# 51.net
KiCad netlist of a schematic drawn in EasyEDA Pro
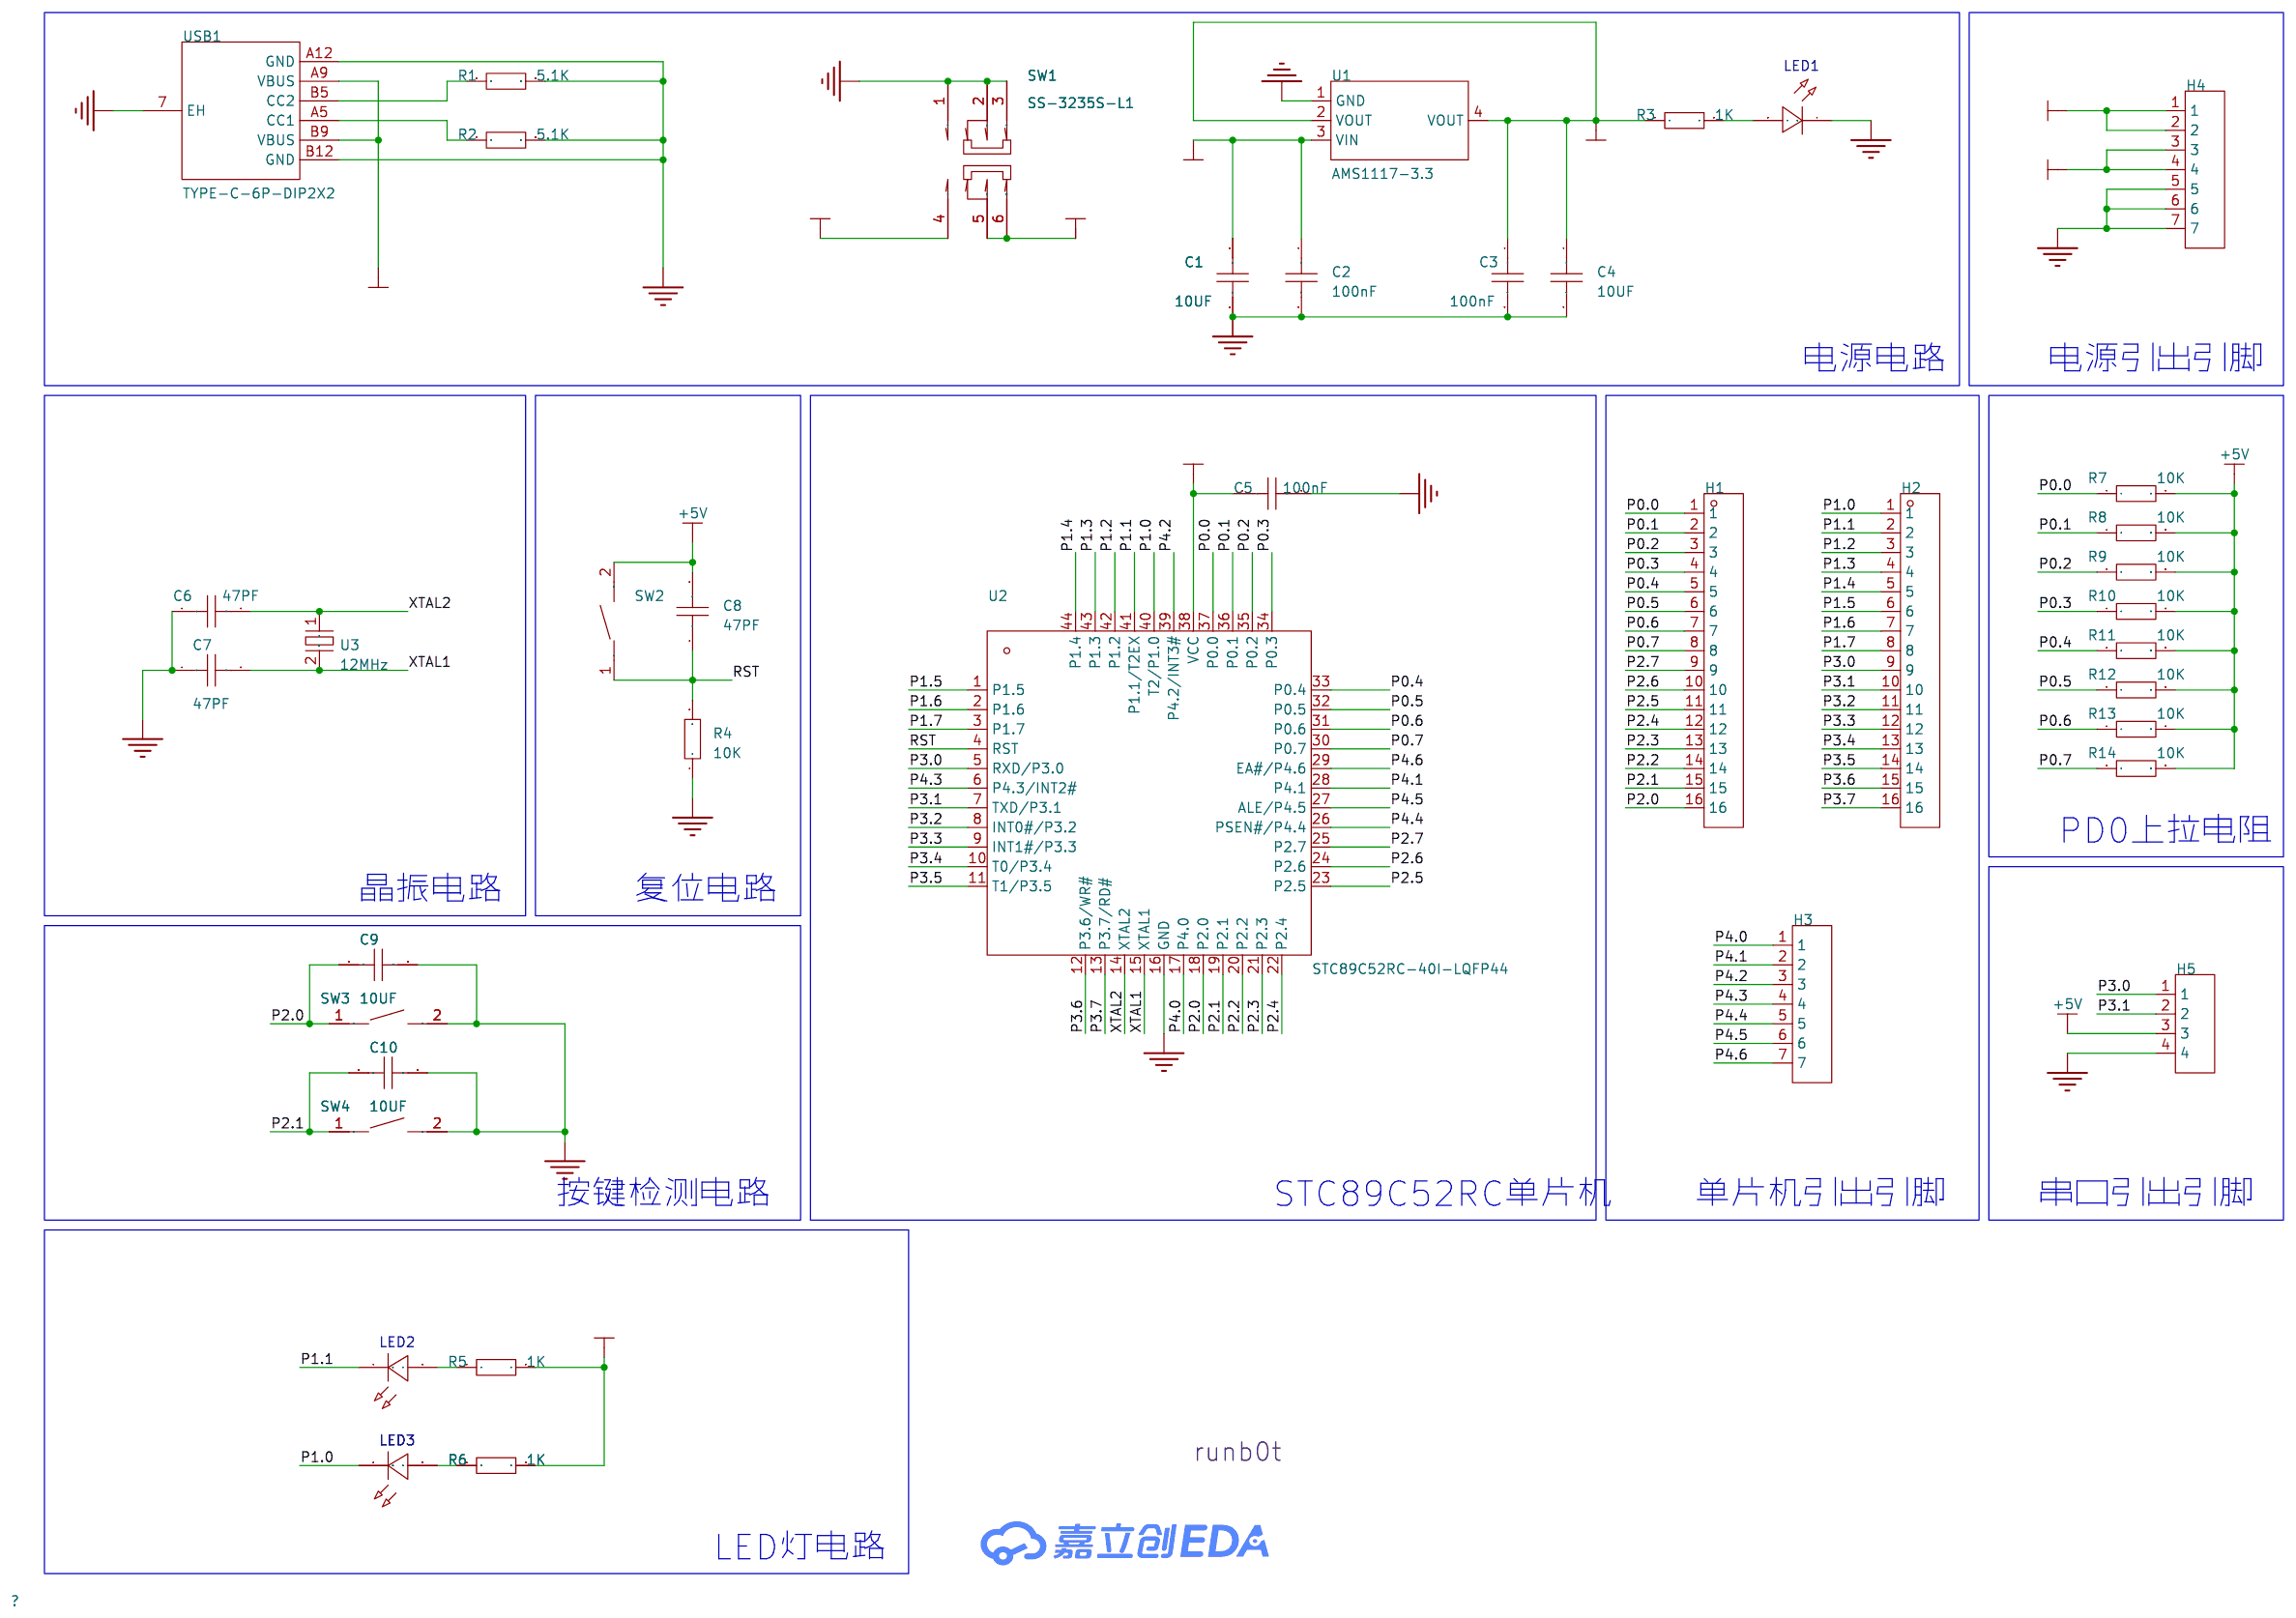
[diagram p0: schematic sheet]

(export (version "E")
  (design (tool "Eeschema 10.0.6"))
  (components
    (comp (ref "C1")
      (value "10UF")
      (footprint "easyedapro:C0805")
      (libsource (lib "easyedapro") (part "CapAcitance"))
    )
    (comp (ref "C2")
      (value "100nF")
      (footprint "easyedapro:C0805")
      (libsource (lib "easyedapro") (part "CapAcitance"))
    )
    (comp (ref "C3")
      (value "100nF")
      (footprint "easyedapro:C0805")
      (libsource (lib "easyedapro") (part "CapAcitance"))
    )
    (comp (ref "C4")
      (value "10UF")
      (footprint "easyedapro:C0805")
      (libsource (lib "easyedapro") (part "CapAcitance"))
    )
    (comp (ref "C5")
      (value "100nF")
      (footprint "easyedapro:C0805")
      (libsource (lib "easyedapro") (part "CapAcitance"))
    )
    (comp (ref "C6")
      (value "47PF")
      (footprint "easyedapro:C0805")
      (libsource (lib "easyedapro") (part "CapAcitance"))
    )
    (comp (ref "C7")
      (value "47PF")
      (footprint "easyedapro:C0805")
      (libsource (lib "easyedapro") (part "CapAcitance"))
    )
    (comp (ref "C8")
      (value "47PF")
      (footprint "easyedapro:C0805")
      (libsource (lib "easyedapro") (part "CapAcitance"))
    )
    (comp (ref "C9")
      (value "10UF")
      (footprint "easyedapro:C0805")
      (libsource (lib "easyedapro") (part "CapAcitance"))
    )
    (comp (ref "C10")
      (value "10UF")
      (footprint "easyedapro:C0805")
      (libsource (lib "easyedapro") (part "CapAcitance"))
    )
    (comp (ref "H1")
      (value "~")
      (footprint "easyedapro:HDR-TH_16P-P2.54-V-M")
      (libsource (lib "easyedapro") (part "HDR_2.54-1x16P"))
    )
    (comp (ref "H2")
      (value "~")
      (footprint "easyedapro:HDR-TH_16P-P2.54-V-M")
      (libsource (lib "easyedapro") (part "HDR_2.54-1x16P"))
    )
    (comp (ref "H3")
      (value "~")
      (footprint "easyedapro:HDR-TH_7P-P2.54-V-M")
      (libsource (lib "easyedapro") (part "PZ254V-11-07P"))
    )
    (comp (ref "H4")
      (value "~")
      (footprint "easyedapro:HDR-TH_7P-P2.54-V-M")
      (libsource (lib "easyedapro") (part "PZ254V-11-07P"))
    )
    (comp (ref "H5")
      (value "~")
      (footprint "easyedapro:HDR-TH_4P-P2.54-V-M")
      (libsource (lib "easyedapro") (part "PZ254V-11-04P"))
    )
    (comp (ref "LED1")
      (value "~")
      (footprint "easyedapro:LED_0805")
      (libsource (lib "easyedapro") (part "LED_G"))
    )
    (comp (ref "LED2")
      (value "~")
      (footprint "easyedapro:LED_0805")
      (libsource (lib "easyedapro") (part "LED_G"))
    )
    (comp (ref "LED3")
      (value "~")
      (footprint "easyedapro:LED_0805")
      (libsource (lib "easyedapro") (part "LED_G"))
    )
    (comp (ref "R1") (value "5.1K") (footprint "easyedapro:R0805") (libsource (lib "easyedapro") (part "电阻")))
    (comp (ref "R2") (value "5.1K") (footprint "easyedapro:R0805") (libsource (lib "easyedapro") (part "电阻")))
    (comp (ref "R3") (value "1K") (footprint "easyedapro:R0805") (libsource (lib "easyedapro") (part "电阻")))
    (comp (ref "R4") (value "10K") (footprint "easyedapro:R0805") (libsource (lib "easyedapro") (part "电阻")))
    (comp (ref "R5") (value "1K") (footprint "easyedapro:R0805") (libsource (lib "easyedapro") (part "电阻")))
    (comp (ref "R6") (value "1K") (footprint "easyedapro:R0805") (libsource (lib "easyedapro") (part "电阻")))
    (comp (ref "R7") (value "10K") (footprint "easyedapro:R0805") (libsource (lib "easyedapro") (part "电阻")))
    (comp (ref "R8") (value "10K") (footprint "easyedapro:R0805") (libsource (lib "easyedapro") (part "电阻")))
    (comp (ref "R9") (value "10K") (footprint "easyedapro:R0805") (libsource (lib "easyedapro") (part "电阻")))
    (comp (ref "R10") (value "10K") (footprint "easyedapro:R0805") (libsource (lib "easyedapro") (part "电阻")))
    (comp (ref "R11") (value "10K") (footprint "easyedapro:R0805") (libsource (lib "easyedapro") (part "电阻")))
    (comp (ref "R12") (value "10K") (footprint "easyedapro:R0805") (libsource (lib "easyedapro") (part "电阻")))
    (comp (ref "R13") (value "10K") (footprint "easyedapro:R0805") (libsource (lib "easyedapro") (part "电阻")))
    (comp (ref "R14") (value "10K") (footprint "easyedapro:R0805") (libsource (lib "easyedapro") (part "电阻")))
    (comp (ref "SW1")
      (value "SS-3235S-L1")
      (footprint "easyedapro:SW-SMD_SS-3235S-LX")
      (description "电路结构:双刀双掷;安装方式:卧贴;开关颜色:黑色;额定电流(DC):50mA;额定电压(DC):12V;额定电流(AC):50mA;额定电压(AC):12V;机械寿命:1万次;")
      (fields (field (name "Manufacturer") "XKB Connectivity(中国星坤)"))
      (libsource (lib "easyedapro") (part "SS-3235S-L1"))
    )
    (comp (ref "SW2")
      (value "轻触按键3*4*H")
      (footprint "easyedapro:SW-SMD_L4.0-W2.9-LS5.0")
      (libsource (lib "easyedapro") (part "轻触按键3*4*H"))
    )
    (comp (ref "SW3")
      (value "轻触按键3*4*H")
      (footprint "easyedapro:SW-SMD_L4.0-W2.9-LS5.0")
      (libsource (lib "easyedapro") (part "轻触按键3*4*H"))
    )
    (comp (ref "SW4")
      (value "轻触按键3*4*H")
      (footprint "easyedapro:SW-SMD_L4.0-W2.9-LS5.0")
      (libsource (lib "easyedapro") (part "轻触按键3*4*H"))
    )
    (comp (ref "U1")
      (value "AMS1117-3.3")
      (footprint "easyedapro:SOT-223-3_L6.5-W3.4-P2.30-LS7.0-BR")
      (description "输出类型:固定;工作电压:-;输出电压:3.3V;输出电流:1A;电源纹波抑制比(PSRR):72dB@(120Hz);输出极性:正极;")
      (fields (field (name "Manufacturer") "AMS"))
      (libsource (lib "easyedapro") (part "AMS1117-3.3"))
    )
    (comp (ref "U2")
      (value "STC89C52RC-40I-LQFP44")
      (footprint "easyedapro:LQFP-44_L10.0-W10.0-P0.80-LS12.0-BL")
      (description "CPU内核:51系列;应用领域:-;")
      (fields (field (name "Manufacturer") "STC"))
      (libsource (lib "easyedapro") (part "STC89C52RC-40I_C8707"))
    )
    (comp (ref "U3")
      (value "12MHz")
      (footprint "easyedapro:CRYSTAL-SMD_L11.4-W4.7-LS12.7")
      (description "频率:12MHz;常温频差:±30ppm;外接负载电容:18pF;频率稳定度(全温):±35ppm;")
      (fields
        (field (name "Manufacturer Part") "ABLS-12.000MHZ-B4H-T")
        (field (name "Manufacturer") "ABRACON")
      )
      (libsource (lib "easyedapro") (part "ABLS-12.000MHZ-B4H-T"))
    )
    (comp (ref "USB1")
      (value "TYPE-C-6P-DIP2X2")
      (footprint "easyedapro:TYPE-C-SMD_TYPE-C-6P")
      (libsource (lib "easyedapro") (part "TYPE-C-6P-DIP2X2"))
    )
  )
  (nets
    (net (code "1") (name "+5V") (class "Default")
      (node (ref "C1") (pin "1") (pinfunction "1_1") (pintype "input"))
      (node (ref "C2") (pin "1") (pinfunction "1_1") (pintype "input"))
      (node (ref "C5") (pin "1") (pinfunction "1_1") (pintype "input"))
      (node (ref "C8") (pin "2") (pinfunction "2_2") (pintype "input"))
      (node (ref "H4") (pin "1") (pinfunction "1_1") (pintype "unspecified"))
      (node (ref "H4") (pin "2") (pinfunction "2_2") (pintype "unspecified"))
      (node (ref "H5") (pin "3") (pinfunction "3_3") (pintype "unspecified"))
      (node (ref "R10") (pin "2") (pinfunction "2_2") (pintype "input"))
      (node (ref "R11") (pin "2") (pinfunction "2_2") (pintype "input"))
      (node (ref "R12") (pin "2") (pinfunction "2_2") (pintype "input"))
      (node (ref "R13") (pin "2") (pinfunction "2_2") (pintype "input"))
      (node (ref "R14") (pin "2") (pinfunction "2_2") (pintype "input"))
      (node (ref "R7") (pin "2") (pinfunction "2_2") (pintype "input"))
      (node (ref "R8") (pin "2") (pinfunction "2_2") (pintype "input"))
      (node (ref "R9") (pin "2") (pinfunction "2_2") (pintype "input"))
      (node (ref "SW1") (pin "5") (pinfunction "5_5") (pintype "unspecified"))
      (node (ref "SW1") (pin "6") (pinfunction "6_6") (pintype "unspecified"))
      (node (ref "SW2") (pin "2") (pinfunction "2_2") (pintype "unspecified"))
      (node (ref "U1") (pin "3") (pinfunction "VIN_3") (pintype "unspecified"))
      (node (ref "U2") (pin "38") (pinfunction "VCC_38") (pintype "unspecified"))
    )
    (net (code "2") (name "/P0.0") (class "Default")
      (node (ref "H1") (pin "1") (pinfunction "1_1") (pintype "input"))
      (node (ref "R7") (pin "1") (pinfunction "1_1") (pintype "input"))
      (node (ref "U2") (pin "37") (pinfunction "P0.0_37") (pintype "unspecified"))
    )
    (net (code "3") (name "/P0.1") (class "Default")
      (node (ref "H1") (pin "2") (pinfunction "2_2") (pintype "input"))
      (node (ref "R8") (pin "1") (pinfunction "1_1") (pintype "input"))
      (node (ref "U2") (pin "36") (pinfunction "P0.1_36") (pintype "unspecified"))
    )
    (net (code "4") (name "/P0.2") (class "Default")
      (node (ref "H1") (pin "3") (pinfunction "3_3") (pintype "input"))
      (node (ref "R9") (pin "1") (pinfunction "1_1") (pintype "input"))
      (node (ref "U2") (pin "35") (pinfunction "P0.2_35") (pintype "unspecified"))
    )
    (net (code "5") (name "/P0.3") (class "Default")
      (node (ref "H1") (pin "4") (pinfunction "4_4") (pintype "input"))
      (node (ref "R10") (pin "1") (pinfunction "1_1") (pintype "input"))
      (node (ref "U2") (pin "34") (pinfunction "P0.3_34") (pintype "unspecified"))
    )
    (net (code "6") (name "/P0.4") (class "Default")
      (node (ref "H1") (pin "5") (pinfunction "5_5") (pintype "input"))
      (node (ref "R11") (pin "1") (pinfunction "1_1") (pintype "input"))
      (node (ref "U2") (pin "33") (pinfunction "P0.4_33") (pintype "unspecified"))
    )
    (net (code "7") (name "/P0.5") (class "Default")
      (node (ref "H1") (pin "6") (pinfunction "6_6") (pintype "input"))
      (node (ref "R12") (pin "1") (pinfunction "1_1") (pintype "input"))
      (node (ref "U2") (pin "32") (pinfunction "P0.5_32") (pintype "unspecified"))
    )
    (net (code "8") (name "/P0.6") (class "Default")
      (node (ref "H1") (pin "7") (pinfunction "7_7") (pintype "input"))
      (node (ref "R13") (pin "1") (pinfunction "1_1") (pintype "input"))
      (node (ref "U2") (pin "31") (pinfunction "P0.6_31") (pintype "unspecified"))
    )
    (net (code "9") (name "/P0.7") (class "Default")
      (node (ref "H1") (pin "8") (pinfunction "8_8") (pintype "input"))
      (node (ref "R14") (pin "1") (pinfunction "1_1") (pintype "input"))
      (node (ref "U2") (pin "30") (pinfunction "P0.7_30") (pintype "unspecified"))
    )
    (net (code "10") (name "/P1.0") (class "Default")
      (node (ref "H2") (pin "1") (pinfunction "1_1") (pintype "input"))
      (node (ref "LED3") (pin "1") (pinfunction "C_1") (pintype "input"))
      (node (ref "U2") (pin "40") (pinfunction "T2/P1.0_40") (pintype "unspecified"))
    )
    (net (code "11") (name "/P1.1") (class "Default")
      (node (ref "H2") (pin "2") (pinfunction "2_2") (pintype "input"))
      (node (ref "LED2") (pin "1") (pinfunction "C_1") (pintype "input"))
      (node (ref "U2") (pin "41") (pinfunction "P1.1/T2EX_41") (pintype "unspecified"))
    )
    (net (code "12") (name "/P1.2") (class "Default")
      (node (ref "H2") (pin "3") (pinfunction "3_3") (pintype "input"))
      (node (ref "U2") (pin "42") (pinfunction "P1.2_42") (pintype "unspecified"))
    )
    (net (code "13") (name "/P1.3") (class "Default")
      (node (ref "H2") (pin "4") (pinfunction "4_4") (pintype "input"))
      (node (ref "U2") (pin "43") (pinfunction "P1.3_43") (pintype "unspecified"))
    )
    (net (code "14") (name "/P1.4") (class "Default")
      (node (ref "H2") (pin "5") (pinfunction "5_5") (pintype "input"))
      (node (ref "U2") (pin "44") (pinfunction "P1.4_44") (pintype "unspecified"))
    )
    (net (code "15") (name "/P1.5") (class "Default")
      (node (ref "H2") (pin "6") (pinfunction "6_6") (pintype "input"))
      (node (ref "U2") (pin "1") (pinfunction "P1.5_1") (pintype "unspecified"))
    )
    (net (code "16") (name "/P1.6") (class "Default")
      (node (ref "H2") (pin "7") (pinfunction "7_7") (pintype "input"))
      (node (ref "U2") (pin "2") (pinfunction "P1.6_2") (pintype "unspecified"))
    )
    (net (code "17") (name "/P1.7") (class "Default")
      (node (ref "H2") (pin "8") (pinfunction "8_8") (pintype "input"))
      (node (ref "U2") (pin "3") (pinfunction "P1.7_3") (pintype "unspecified"))
    )
    (net (code "18") (name "/P2.0") (class "Default")
      (node (ref "C9") (pin "1") (pinfunction "1_1") (pintype "input"))
      (node (ref "H1") (pin "16") (pinfunction "16_16") (pintype "input"))
      (node (ref "SW3") (pin "1") (pinfunction "1_1") (pintype "unspecified"))
      (node (ref "U2") (pin "18") (pinfunction "P2.0_18") (pintype "unspecified"))
    )
    (net (code "19") (name "/P2.1") (class "Default")
      (node (ref "C10") (pin "1") (pinfunction "1_1") (pintype "input"))
      (node (ref "H1") (pin "15") (pinfunction "15_15") (pintype "input"))
      (node (ref "SW4") (pin "1") (pinfunction "1_1") (pintype "unspecified"))
      (node (ref "U2") (pin "19") (pinfunction "P2.1_19") (pintype "unspecified"))
    )
    (net (code "20") (name "/P2.2") (class "Default")
      (node (ref "H1") (pin "14") (pinfunction "14_14") (pintype "input"))
      (node (ref "U2") (pin "20") (pinfunction "P2.2_20") (pintype "unspecified"))
    )
    (net (code "21") (name "/P2.3") (class "Default")
      (node (ref "H1") (pin "13") (pinfunction "13_13") (pintype "input"))
      (node (ref "U2") (pin "21") (pinfunction "P2.3_21") (pintype "unspecified"))
    )
    (net (code "22") (name "/P2.4") (class "Default")
      (node (ref "H1") (pin "12") (pinfunction "12_12") (pintype "input"))
      (node (ref "U2") (pin "22") (pinfunction "P2.4_22") (pintype "unspecified"))
    )
    (net (code "23") (name "/P2.5") (class "Default")
      (node (ref "H1") (pin "11") (pinfunction "11_11") (pintype "input"))
      (node (ref "U2") (pin "23") (pinfunction "P2.5_23") (pintype "unspecified"))
    )
    (net (code "24") (name "/P2.6") (class "Default")
      (node (ref "H1") (pin "10") (pinfunction "10_10") (pintype "input"))
      (node (ref "U2") (pin "24") (pinfunction "P2.6_24") (pintype "unspecified"))
    )
    (net (code "25") (name "/P2.7") (class "Default")
      (node (ref "H1") (pin "9") (pinfunction "9_9") (pintype "input"))
      (node (ref "U2") (pin "25") (pinfunction "P2.7_25") (pintype "unspecified"))
    )
    (net (code "26") (name "/P3.0") (class "Default")
      (node (ref "H2") (pin "9") (pinfunction "9_9") (pintype "input"))
      (node (ref "H5") (pin "1") (pinfunction "1_1") (pintype "unspecified"))
      (node (ref "U2") (pin "5") (pinfunction "RXD/P3.0_5") (pintype "unspecified"))
    )
    (net (code "27") (name "/P3.1") (class "Default")
      (node (ref "H2") (pin "10") (pinfunction "10_10") (pintype "input"))
      (node (ref "H5") (pin "2") (pinfunction "2_2") (pintype "unspecified"))
      (node (ref "U2") (pin "7") (pinfunction "TXD/P3.1_7") (pintype "unspecified"))
    )
    (net (code "28") (name "/P3.2") (class "Default")
      (node (ref "H2") (pin "11") (pinfunction "11_11") (pintype "input"))
      (node (ref "U2") (pin "8") (pinfunction "INT0#/P3.2_8") (pintype "unspecified"))
    )
    (net (code "29") (name "/P3.3") (class "Default")
      (node (ref "H2") (pin "12") (pinfunction "12_12") (pintype "input"))
      (node (ref "U2") (pin "9") (pinfunction "INT1#/P3.3_9") (pintype "unspecified"))
    )
    (net (code "30") (name "/P3.4") (class "Default")
      (node (ref "H2") (pin "13") (pinfunction "13_13") (pintype "input"))
      (node (ref "U2") (pin "10") (pinfunction "T0/P3.4_10") (pintype "unspecified"))
    )
    (net (code "31") (name "/P3.5") (class "Default")
      (node (ref "H2") (pin "14") (pinfunction "14_14") (pintype "input"))
      (node (ref "U2") (pin "11") (pinfunction "T1/P3.5_11") (pintype "unspecified"))
    )
    (net (code "32") (name "/P3.6") (class "Default")
      (node (ref "H2") (pin "15") (pinfunction "15_15") (pintype "input"))
      (node (ref "U2") (pin "12") (pinfunction "P3.6/WR#_12") (pintype "unspecified"))
    )
    (net (code "33") (name "/P3.7") (class "Default")
      (node (ref "H2") (pin "16") (pinfunction "16_16") (pintype "input"))
      (node (ref "U2") (pin "13") (pinfunction "P3.7/RD#_13") (pintype "unspecified"))
    )
    (net (code "34") (name "/P4.0") (class "Default")
      (node (ref "H3") (pin "1") (pinfunction "1_1") (pintype "unspecified"))
      (node (ref "U2") (pin "17") (pinfunction "P4.0_17") (pintype "unspecified"))
    )
    (net (code "35") (name "/P4.1") (class "Default")
      (node (ref "H3") (pin "2") (pinfunction "2_2") (pintype "unspecified"))
      (node (ref "U2") (pin "28") (pinfunction "P4.1_28") (pintype "unspecified"))
    )
    (net (code "36") (name "/P4.2") (class "Default")
      (node (ref "H3") (pin "3") (pinfunction "3_3") (pintype "unspecified"))
      (node (ref "U2") (pin "39") (pinfunction "P4.2/INT3#_39") (pintype "unspecified"))
    )
    (net (code "37") (name "/P4.3") (class "Default")
      (node (ref "H3") (pin "4") (pinfunction "4_4") (pintype "unspecified"))
      (node (ref "U2") (pin "6") (pinfunction "P4.3/INT2#_6") (pintype "unspecified"))
    )
    (net (code "38") (name "/P4.4") (class "Default")
      (node (ref "H3") (pin "5") (pinfunction "5_5") (pintype "unspecified"))
      (node (ref "U2") (pin "26") (pinfunction "PSEN#/P4.4_26") (pintype "unspecified"))
    )
    (net (code "39") (name "/P4.5") (class "Default")
      (node (ref "H3") (pin "6") (pinfunction "6_6") (pintype "unspecified"))
      (node (ref "U2") (pin "27") (pinfunction "ALE/P4.5_27") (pintype "unspecified"))
    )
    (net (code "40") (name "/P4.6") (class "Default")
      (node (ref "H3") (pin "7") (pinfunction "7_7") (pintype "unspecified"))
      (node (ref "U2") (pin "29") (pinfunction "EA#/P4.6_29") (pintype "unspecified"))
    )
    (net (code "41") (name "/RST") (class "Default")
      (node (ref "C8") (pin "1") (pinfunction "1_1") (pintype "input"))
      (node (ref "R4") (pin "2") (pinfunction "2_2") (pintype "input"))
      (node (ref "SW2") (pin "1") (pinfunction "1_1") (pintype "unspecified"))
      (node (ref "U2") (pin "4") (pinfunction "RST_4") (pintype "unspecified"))
    )
    (net (code "42") (name "/XTAL1") (class "Default")
      (node (ref "C7") (pin "2") (pinfunction "2_2") (pintype "input"))
      (node (ref "U2") (pin "15") (pinfunction "XTAL1_15") (pintype "unspecified"))
      (node (ref "U3") (pin "2") (pinfunction "GND_2") (pintype "input"))
    )
    (net (code "43") (name "/XTAL2") (class "Default")
      (node (ref "C6") (pin "2") (pinfunction "2_2") (pintype "input"))
      (node (ref "U2") (pin "14") (pinfunction "XTAL2_14") (pintype "unspecified"))
      (node (ref "U3") (pin "1") (pinfunction "1_1") (pintype "input"))
    )
    (net (code "44") (name "3.3V") (class "Default")
      (node (ref "C3") (pin "1") (pinfunction "1_1") (pintype "input"))
      (node (ref "C4") (pin "1") (pinfunction "1_1") (pintype "input"))
      (node (ref "H4") (pin "3") (pinfunction "3_3") (pintype "unspecified"))
      (node (ref "H4") (pin "4") (pinfunction "4_4") (pintype "unspecified"))
      (node (ref "R3") (pin "1") (pinfunction "1_1") (pintype "input"))
      (node (ref "R5") (pin "2") (pinfunction "2_2") (pintype "input"))
      (node (ref "R6") (pin "2") (pinfunction "2_2") (pintype "input"))
      (node (ref "U1") (pin "2") (pinfunction "VOUT_2") (pintype "unspecified"))
      (node (ref "U1") (pin "4") (pinfunction "VOUT_4") (pintype "unspecified"))
    )
    (net (code "45") (name "GND") (class "Default")
      (node (ref "C1") (pin "2") (pinfunction "2_2") (pintype "input"))
      (node (ref "C10") (pin "2") (pinfunction "2_2") (pintype "input"))
      (node (ref "C2") (pin "2") (pinfunction "2_2") (pintype "input"))
      (node (ref "C3") (pin "2") (pinfunction "2_2") (pintype "input"))
      (node (ref "C4") (pin "2") (pinfunction "2_2") (pintype "input"))
      (node (ref "C5") (pin "2") (pinfunction "2_2") (pintype "input"))
      (node (ref "C6") (pin "1") (pinfunction "1_1") (pintype "input"))
      (node (ref "C7") (pin "1") (pinfunction "1_1") (pintype "input"))
      (node (ref "C9") (pin "2") (pinfunction "2_2") (pintype "input"))
      (node (ref "H4") (pin "5") (pinfunction "5_5") (pintype "unspecified"))
      (node (ref "H4") (pin "6") (pinfunction "6_6") (pintype "unspecified"))
      (node (ref "H4") (pin "7") (pinfunction "7_7") (pintype "unspecified"))
      (node (ref "H5") (pin "4") (pinfunction "4_4") (pintype "unspecified"))
      (node (ref "LED1") (pin "1") (pinfunction "C_1") (pintype "input"))
      (node (ref "R1") (pin "2") (pinfunction "2_2") (pintype "input"))
      (node (ref "R2") (pin "2") (pinfunction "2_2") (pintype "input"))
      (node (ref "R4") (pin "1") (pinfunction "1_1") (pintype "input"))
      (node (ref "SW1") (pin "1") (pinfunction "1_1") (pintype "unspecified"))
      (node (ref "SW1") (pin "2") (pinfunction "2_2") (pintype "unspecified"))
      (node (ref "SW1") (pin "3") (pinfunction "3_3") (pintype "unspecified"))
      (node (ref "SW3") (pin "2") (pinfunction "2_2") (pintype "unspecified"))
      (node (ref "SW4") (pin "2") (pinfunction "2_2") (pintype "unspecified"))
      (node (ref "U1") (pin "1") (pinfunction "GND_1") (pintype "unspecified"))
      (node (ref "U2") (pin "16") (pinfunction "GND_16") (pintype "unspecified"))
      (node (ref "USB1") (pin "7") (pinfunction "EH_7") (pintype "unspecified"))
      (node (ref "USB1") (pin "A12") (pinfunction "GND_A12") (pintype "unspecified"))
      (node (ref "USB1") (pin "B12") (pinfunction "GND_B12") (pintype "unspecified"))
    )
    (net (code "46") (name "Net-(LED1-A)") (class "Default")
      (node (ref "LED1") (pin "2") (pinfunction "A_2") (pintype "input"))
      (node (ref "R3") (pin "2") (pinfunction "2_2") (pintype "input"))
    )
    (net (code "47") (name "Net-(LED2-A)") (class "Default")
      (node (ref "LED2") (pin "2") (pinfunction "A_2") (pintype "input"))
      (node (ref "R5") (pin "1") (pinfunction "1_1") (pintype "input"))
    )
    (net (code "48") (name "Net-(LED3-A)") (class "Default")
      (node (ref "LED3") (pin "2") (pinfunction "A_2") (pintype "input"))
      (node (ref "R6") (pin "1") (pinfunction "1_1") (pintype "input"))
    )
    (net (code "49") (name "Net-(USB1-CC1)") (class "Default")
      (node (ref "R2") (pin "1") (pinfunction "1_1") (pintype "input"))
      (node (ref "USB1") (pin "A5") (pinfunction "CC1_A5") (pintype "unspecified"))
    )
    (net (code "50") (name "Net-(USB1-CC2)") (class "Default")
      (node (ref "R1") (pin "1") (pinfunction "1_1") (pintype "input"))
      (node (ref "USB1") (pin "B5") (pinfunction "CC2_B5") (pintype "unspecified"))
    )
    (net (code "51") (name "VCC+5V") (class "Default")
      (node (ref "SW1") (pin "4") (pinfunction "4_4") (pintype "unspecified"))
      (node (ref "USB1") (pin "A9") (pinfunction "VBUS_A9") (pintype "unspecified"))
      (node (ref "USB1") (pin "B9") (pinfunction "VBUS_B9") (pintype "unspecified"))
    )
  )
)
